# CPU.net
KiCad netlist of a schematic drawn in Altium Designer
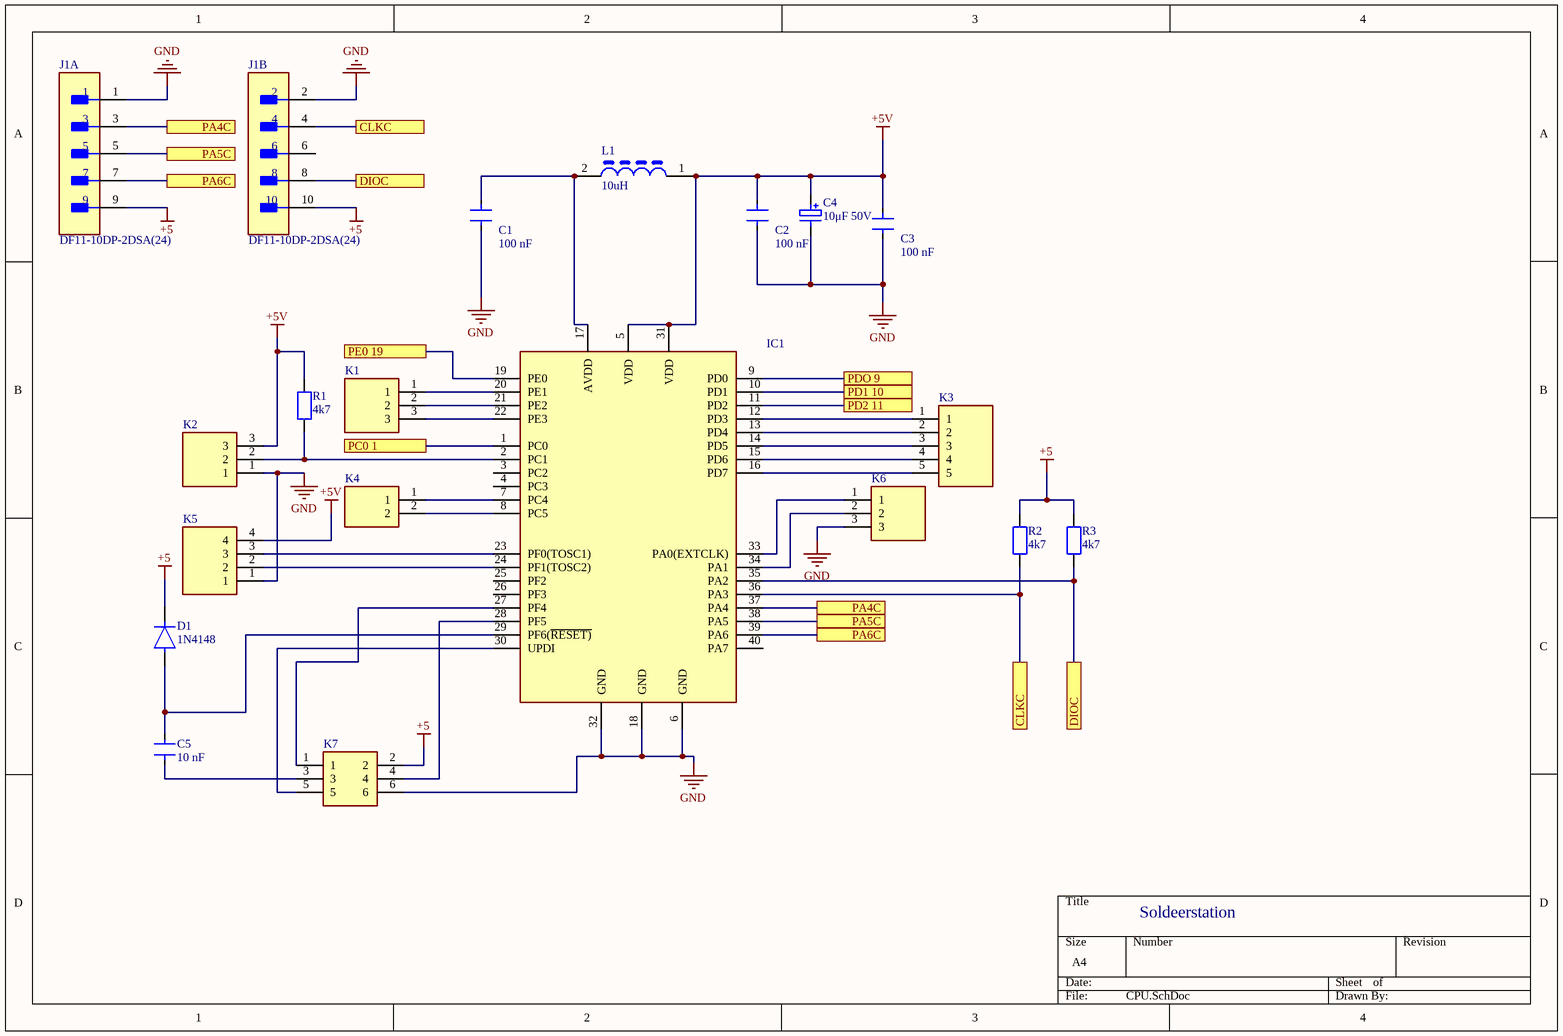
[diagram p0: CPU.SchDoc]

(export (version "E")
  (design (tool "Eeschema 10.0.6"))
  (components
    (comp (ref "C1")
      (value "100 nF")
      (footprint "0805")
      (description "Chip Multilayer Ceramic Capacitors for General Purpose, 0805, 10uF, X5R, 15%, 10%, 25V")
      (fields (field (name "VOLTAGE") "25V") (field (name "TOLERANCE") "10%"))
      (libsource (lib "Soldeerstation") (part "Condensator 0805"))
    )
    (comp (ref "C2")
      (value "100 nF")
      (footprint "0805")
      (description "Chip Multilayer Ceramic Capacitors for General Purpose, 0805, 10uF, X5R, 15%, 10%, 25V")
      (fields (field (name "VOLTAGE") "25V") (field (name "TOLERANCE") "10%"))
      (libsource (lib "Soldeerstation") (part "Condensator 0805"))
    )
    (comp (ref "C3")
      (value "100 nF")
      (footprint "0805")
      (description "Chip Multilayer Ceramic Capacitors for General Purpose, 0805, 10uF, X5R, 15%, 10%, 25V")
      (fields (field (name "VOLTAGE") "25V") (field (name "TOLERANCE") "10%"))
      (libsource (lib "Soldeerstation") (part "Condensator 0805"))
    )
    (comp (ref "C4")
      (value "10μF 50V")
      (footprint "Elco 10uF 50V")
      (fields
        (field (name "PART NUMBER") "02015A270JAT2A")
        (field (name "MANUFACTURER") "AVX Interconnect / Elco")
      )
      (libsource (lib "Soldeerstation") (part "Condensator Elco"))
    )
    (comp (ref "C5")
      (value "10 nF")
      (footprint "0805")
      (description "Chip Multilayer Ceramic Capacitors for General Purpose, 0805, 10uF, X5R, 15%, 10%, 25V")
      (fields (field (name "VOLTAGE") "25V") (field (name "TOLERANCE") "10%"))
      (libsource (lib "Soldeerstation") (part "Condensator 0805"))
    )
    (comp (ref "D1")
      (value "1N4148")
      (footprint "1N4148")
      (description "1N4148, 100 V, 200 mA, 4 ns")
      (fields (field (name "VOLTAGE") "100V"))
      (libsource (lib "Soldeerstation") (part "1N4148"))
    )
    (comp (ref "IC1")
      (value "ATMEGA4809-PF")
      (footprint "IC3")
      (description "ATmega4809-PF")
      (libsource (lib "Soldeerstation") (part "IC3"))
    )
    (comp (ref "J1")
      (value "DF11-10DP-2DSA(24)")
      (footprint "FP-DF11-10DP-2DSA_24-MFG")
      (description "CONN HEADER VERT 10POS 2MM")
      (fields
        (field (name "OCTOPART") "https://octopart.com/df11-10dp-2dsa%2824%29-hirose-39521433")
        (field (name "MANUFACTURER") "Hirose")
      )
      (libsource (lib "Soldeerstation") (part "CMP-11610-000008-1"))
    )
    (comp (ref "K1")
      (value "5-146280-3")
      (footprint "3 Pin Header")
      (description "Connector 5-146280-3")
      (fields (field (name "MOUSER2 PART NUMBER") "571-5-146280-3"))
      (libsource (lib "Soldeerstation") (part "3 Pin Header"))
    )
    (comp (ref "K2")
      (value "5-146280-3")
      (footprint "3 Pin Header")
      (description "Connector 5-146280-3")
      (fields (field (name "MOUSER2 PART NUMBER") "571-5-146280-3"))
      (libsource (lib "") (part "3 Pin Header_1"))
    )
    (comp (ref "K3")
      (value "5-146280-5")
      (footprint "5 Pin Header")
      (description "Connector 5-146280-5")
      (fields (field (name "MOUSER2 PART NUMBER") "571-5-146280-5"))
      (libsource (lib "Soldeerstation") (part "5 Pin Header"))
    )
    (comp (ref "K4")
      (value "5-146280-2")
      (footprint "2 Pin Header")
      (description "Connector")
      (libsource (lib "Soldeerstation") (part "2 Pin Header"))
    )
    (comp (ref "K5")
      (value "5-146280-4")
      (footprint "4 Pin Header")
      (description "Connector 5-146280-4")
      (libsource (lib "Soldeerstation") (part "4 Pin Header"))
    )
    (comp (ref "K6")
      (value "5-146280-3")
      (footprint "3 Pin Header")
      (description "Connector 5-146280-3")
      (fields (field (name "MOUSER2 PART NUMBER") "571-5-146280-3"))
      (libsource (lib "") (part "3 Pin Header_2"))
    )
    (comp (ref "K7")
      (value "2x3 Pin Header")
      (footprint "2x3 Pin Header")
      (description "Connector")
      (fields (field (name "MANUFACTURER_PART_NUMBER") "5-146256-3"))
      (libsource (lib "Soldeerstation") (part "2x3 Pin Header"))
    )
    (comp (ref "L1")
      (value "10uH")
      (footprint "Smoorspoel")
      (description "Inductor VLS6045EX-100M-H")
      (fields
        (field (name "MOUSER2 PART NUMBER") "810-VLS6045EX-100M-H")
        (field (name "MANUFACTURER_PART_NUMBER") "VLS6045EX-100M-H")
      )
      (libsource (lib "Soldeerstation") (part "Smoorspoel"))
    )
    (comp (ref "R1")
      (value "4k7")
      (footprint "Resistor")
      (description "Resistor")
      (fields (field (name "MANUFACTURER") "Vishay Dale") (field (name "PART NUMBER") "CRCW08050000Z0EA"))
      (libsource (lib "Soldeerstation") (part "Resistor"))
    )
    (comp (ref "R2")
      (value "4k7")
      (footprint "Resistor")
      (description "Resistor")
      (fields (field (name "MANUFACTURER") "Vishay Dale") (field (name "PART NUMBER") "CRCW08050000Z0EA"))
      (libsource (lib "Soldeerstation") (part "Resistor"))
    )
    (comp (ref "R3")
      (value "4k7")
      (footprint "Resistor")
      (description "Resistor")
      (fields (field (name "MANUFACTURER") "Vishay Dale") (field (name "PART NUMBER") "CRCW08050000Z0EA"))
      (libsource (lib "Soldeerstation") (part "Resistor"))
    )
  )
  (nets
    (net (code "1") (name "+5") (class "Default")
      (node (ref "D1") (pin "1") (pinfunction "C_1") (pintype "passive"))
      (node (ref "J1") (pin "10") (pinfunction "10_10") (pintype "passive"))
      (node (ref "J1") (pin "9") (pinfunction "9_9") (pintype "passive"))
      (node (ref "K7") (pin "2") (pinfunction "2_2") (pintype "passive"))
      (node (ref "R2") (pin "2") (pinfunction "2_2") (pintype "passive"))
      (node (ref "R3") (pin "2") (pinfunction "2_2") (pintype "passive"))
    )
    (net (code "2") (name "+5V") (class "Default")
      (node (ref "C2") (pin "1") (pinfunction "1_1") (pintype "passive"))
      (node (ref "C3") (pin "1") (pinfunction "1_1") (pintype "passive"))
      (node (ref "C4") (pin "1") (pinfunction "1_1") (pintype "passive"))
      (node (ref "IC1") (pin "31") (pinfunction "VDD_31") (pintype "power_in"))
      (node (ref "IC1") (pin "5") (pinfunction "VDD_5") (pintype "power_in"))
      (node (ref "K2") (pin "3") (pinfunction "3_3") (pintype "passive"))
      (node (ref "K5") (pin "4") (pinfunction "4_4") (pintype "passive"))
      (node (ref "L1") (pin "1") (pinfunction "1_1") (pintype "passive"))
      (node (ref "R1") (pin "2") (pinfunction "2_2") (pintype "passive"))
    )
    (net (code "3") (name "/CLKC") (class "Default")
      (node (ref "IC1") (pin "36") (pinfunction "PA3_36") (pintype "power_in"))
      (node (ref "J1") (pin "4") (pinfunction "4_4") (pintype "passive"))
      (node (ref "R2") (pin "1") (pintype "passive"))
    )
    (net (code "4") (name "/DIOC") (class "Default")
      (node (ref "IC1") (pin "35") (pinfunction "PA2_35") (pintype "power_in"))
      (node (ref "J1") (pin "8") (pinfunction "8_8") (pintype "passive"))
      (node (ref "R3") (pin "1") (pintype "passive"))
    )
    (net (code "5") (name "/PA4C") (class "Default")
      (node (ref "IC1") (pin "37") (pinfunction "PA4_37") (pintype "power_in"))
      (node (ref "J1") (pin "3") (pinfunction "3_3") (pintype "passive"))
    )
    (net (code "6") (name "/PA5C") (class "Default")
      (node (ref "IC1") (pin "38") (pinfunction "PA5_38") (pintype "power_in"))
      (node (ref "J1") (pin "5") (pinfunction "5_5") (pintype "passive"))
    )
    (net (code "7") (name "/PA6C") (class "Default")
      (node (ref "IC1") (pin "39") (pinfunction "PA6_39") (pintype "power_in"))
      (node (ref "J1") (pin "7") (pinfunction "7_7") (pintype "passive"))
    )
    (net (code "8") (name "/PC0 1") (class "Default")
      (node (ref "IC1") (pin "1") (pinfunction "PC0_1") (pintype "passive"))
    )
    (net (code "9") (name "/PD1 10") (class "Default")
      (node (ref "IC1") (pin "10") (pinfunction "PD1_10") (pintype "power_in"))
    )
    (net (code "10") (name "/PD2 11") (class "Default")
      (node (ref "IC1") (pin "11") (pinfunction "PD2_11") (pintype "power_in"))
    )
    (net (code "11") (name "/PDO 9") (class "Default")
      (node (ref "IC1") (pin "9") (pinfunction "PD0_9") (pintype "power_in"))
    )
    (net (code "12") (name "/PE0 19") (class "Default")
      (node (ref "IC1") (pin "19") (pinfunction "PE0_19") (pintype "passive"))
    )
    (net (code "13") (name "GND") (class "Default")
      (node (ref "C1") (pin "2") (pinfunction "2_2") (pintype "passive"))
      (node (ref "C2") (pin "2") (pinfunction "2_2") (pintype "passive"))
      (node (ref "C3") (pin "2") (pinfunction "2_2") (pintype "passive"))
      (node (ref "C4") (pin "2") (pinfunction "2_2") (pintype "passive"))
      (node (ref "IC1") (pin "18") (pinfunction "GND_18") (pintype "power_in"))
      (node (ref "IC1") (pin "32") (pinfunction "GND_32") (pintype "power_in"))
      (node (ref "IC1") (pin "6") (pinfunction "GND_6") (pintype "power_in"))
      (node (ref "J1") (pin "1") (pinfunction "1_1") (pintype "passive"))
      (node (ref "J1") (pin "2") (pinfunction "2_2") (pintype "passive"))
      (node (ref "K2") (pin "1") (pinfunction "1_1") (pintype "passive"))
      (node (ref "K5") (pin "1") (pinfunction "1_1") (pintype "passive"))
      (node (ref "K6") (pin "3") (pinfunction "3_3") (pintype "passive"))
      (node (ref "K7") (pin "6") (pinfunction "6_6") (pintype "passive"))
    )
    (net (code "14") (name "Net-(C5-Pad1)") (class "Default")
      (node (ref "C5") (pin "1") (pinfunction "1_1") (pintype "passive"))
      (node (ref "K7") (pin "3") (pinfunction "3_3") (pintype "passive"))
    )
    (net (code "15") (name "Net-(D1-A)") (class "Default")
      (node (ref "C5") (pin "2") (pinfunction "2_2") (pintype "passive"))
      (node (ref "D1") (pin "2") (pinfunction "A_2") (pintype "passive"))
      (node (ref "IC1") (pin "29") (pinfunction "PF6(~{RESET)}_29") (pintype "passive"))
    )
    (net (code "16") (name "Net-(IC1-AVDD)") (class "Default")
      (node (ref "C1") (pin "1") (pinfunction "1_1") (pintype "passive"))
      (node (ref "IC1") (pin "17") (pinfunction "AVDD_17") (pintype "power_in"))
      (node (ref "L1") (pin "2") (pinfunction "2_2") (pintype "passive"))
    )
    (net (code "17") (name "Net-(IC1-PA0(EXTCLK))") (class "Default")
      (node (ref "IC1") (pin "33") (pinfunction "PA0(EXTCLK)_33") (pintype "power_in"))
      (node (ref "K6") (pin "1") (pinfunction "1_1") (pintype "passive"))
    )
    (net (code "18") (name "Net-(IC1-PA1)") (class "Default")
      (node (ref "IC1") (pin "34") (pinfunction "PA1_34") (pintype "power_in"))
      (node (ref "K6") (pin "2") (pinfunction "2_2") (pintype "passive"))
    )
    (net (code "19") (name "Net-(IC1-PC1)") (class "Default")
      (node (ref "IC1") (pin "2") (pinfunction "PC1_2") (pintype "passive"))
      (node (ref "K2") (pin "2") (pinfunction "2_2") (pintype "passive"))
      (node (ref "R1") (pin "1") (pintype "passive"))
    )
    (net (code "20") (name "Net-(IC1-PC4)") (class "Default")
      (node (ref "IC1") (pin "7") (pinfunction "PC4_7") (pintype "passive"))
      (node (ref "K4") (pin "1") (pinfunction "1_1") (pintype "passive"))
    )
    (net (code "21") (name "Net-(IC1-PC5)") (class "Default")
      (node (ref "IC1") (pin "8") (pinfunction "PC5_8") (pintype "passive"))
      (node (ref "K4") (pin "2") (pinfunction "2_2") (pintype "passive"))
    )
    (net (code "22") (name "Net-(IC1-PD3)") (class "Default")
      (node (ref "IC1") (pin "12") (pinfunction "PD3_12") (pintype "power_in"))
      (node (ref "K3") (pin "1") (pinfunction "1_1") (pintype "passive"))
    )
    (net (code "23") (name "Net-(IC1-PD4)") (class "Default")
      (node (ref "IC1") (pin "13") (pinfunction "PD4_13") (pintype "power_in"))
      (node (ref "K3") (pin "2") (pinfunction "2_2") (pintype "passive"))
    )
    (net (code "24") (name "Net-(IC1-PD5)") (class "Default")
      (node (ref "IC1") (pin "14") (pinfunction "PD5_14") (pintype "power_in"))
      (node (ref "K3") (pin "3") (pinfunction "3_3") (pintype "passive"))
    )
    (net (code "25") (name "Net-(IC1-PD6)") (class "Default")
      (node (ref "IC1") (pin "15") (pinfunction "PD6_15") (pintype "power_in"))
      (node (ref "K3") (pin "4") (pinfunction "4_4") (pintype "passive"))
    )
    (net (code "26") (name "Net-(IC1-PD7)") (class "Default")
      (node (ref "IC1") (pin "16") (pinfunction "PD7_16") (pintype "power_in"))
      (node (ref "K3") (pin "5") (pinfunction "5_5") (pintype "passive"))
    )
    (net (code "27") (name "Net-(IC1-PE1)") (class "Default")
      (node (ref "IC1") (pin "20") (pinfunction "PE1_20") (pintype "power_in"))
      (node (ref "K1") (pin "1") (pinfunction "1_1") (pintype "passive"))
    )
    (net (code "28") (name "Net-(IC1-PE2)") (class "Default")
      (node (ref "IC1") (pin "21") (pinfunction "PE2_21") (pintype "passive"))
      (node (ref "K1") (pin "2") (pinfunction "2_2") (pintype "passive"))
    )
    (net (code "29") (name "Net-(IC1-PE3)") (class "Default")
      (node (ref "IC1") (pin "22") (pinfunction "PE3_22") (pintype "passive"))
      (node (ref "K1") (pin "3") (pinfunction "3_3") (pintype "passive"))
    )
    (net (code "30") (name "Net-(IC1-PF0(TOSC1))") (class "Default")
      (node (ref "IC1") (pin "23") (pinfunction "PF0(TOSC1)_23") (pintype "passive"))
      (node (ref "K5") (pin "3") (pinfunction "3_3") (pintype "passive"))
    )
    (net (code "31") (name "Net-(IC1-PF1(TOSC2))") (class "Default")
      (node (ref "IC1") (pin "24") (pinfunction "PF1(TOSC2)_24") (pintype "passive"))
      (node (ref "K5") (pin "2") (pinfunction "2_2") (pintype "passive"))
    )
    (net (code "32") (name "Net-(IC1-PF4)") (class "Default")
      (node (ref "IC1") (pin "27") (pinfunction "PF4_27") (pintype "passive"))
      (node (ref "K7") (pin "1") (pinfunction "1_1") (pintype "passive"))
    )
    (net (code "33") (name "Net-(IC1-PF5)") (class "Default")
      (node (ref "IC1") (pin "28") (pinfunction "PF5_28") (pintype "passive"))
      (node (ref "K7") (pin "4") (pinfunction "4_4") (pintype "passive"))
    )
    (net (code "34") (name "Net-(IC1-UPDI)") (class "Default")
      (node (ref "IC1") (pin "30") (pinfunction "UPDI_30") (pintype "passive"))
      (node (ref "K7") (pin "5") (pinfunction "5_5") (pintype "passive"))
    )
    (net (code "35") (name "unconnected-(IC1-PA7-Pad40)") (class "Default")
      (node (ref "IC1") (pin "40") (pinfunction "PA7_40") (pintype "power_in"))
    )
    (net (code "36") (name "unconnected-(IC1-PC2-Pad3)") (class "Default")
      (node (ref "IC1") (pin "3") (pinfunction "PC2_3") (pintype "passive"))
    )
    (net (code "37") (name "unconnected-(IC1-PC3-Pad4)") (class "Default")
      (node (ref "IC1") (pin "4") (pinfunction "PC3_4") (pintype "passive"))
    )
    (net (code "38") (name "unconnected-(IC1-PF2-Pad25)") (class "Default")
      (node (ref "IC1") (pin "25") (pinfunction "PF2_25") (pintype "passive"))
    )
    (net (code "39") (name "unconnected-(IC1-PF3-Pad26)") (class "Default")
      (node (ref "IC1") (pin "26") (pinfunction "PF3_26") (pintype "passive"))
    )
    (net (code "40") (name "unconnected-(J1-Pad6)") (class "Default")
      (node (ref "J1") (pin "6") (pinfunction "6_6") (pintype "passive"))
    )
  )
)
